# Sheet1.net
KiCad netlist of a schematic drawn in Altium Designer
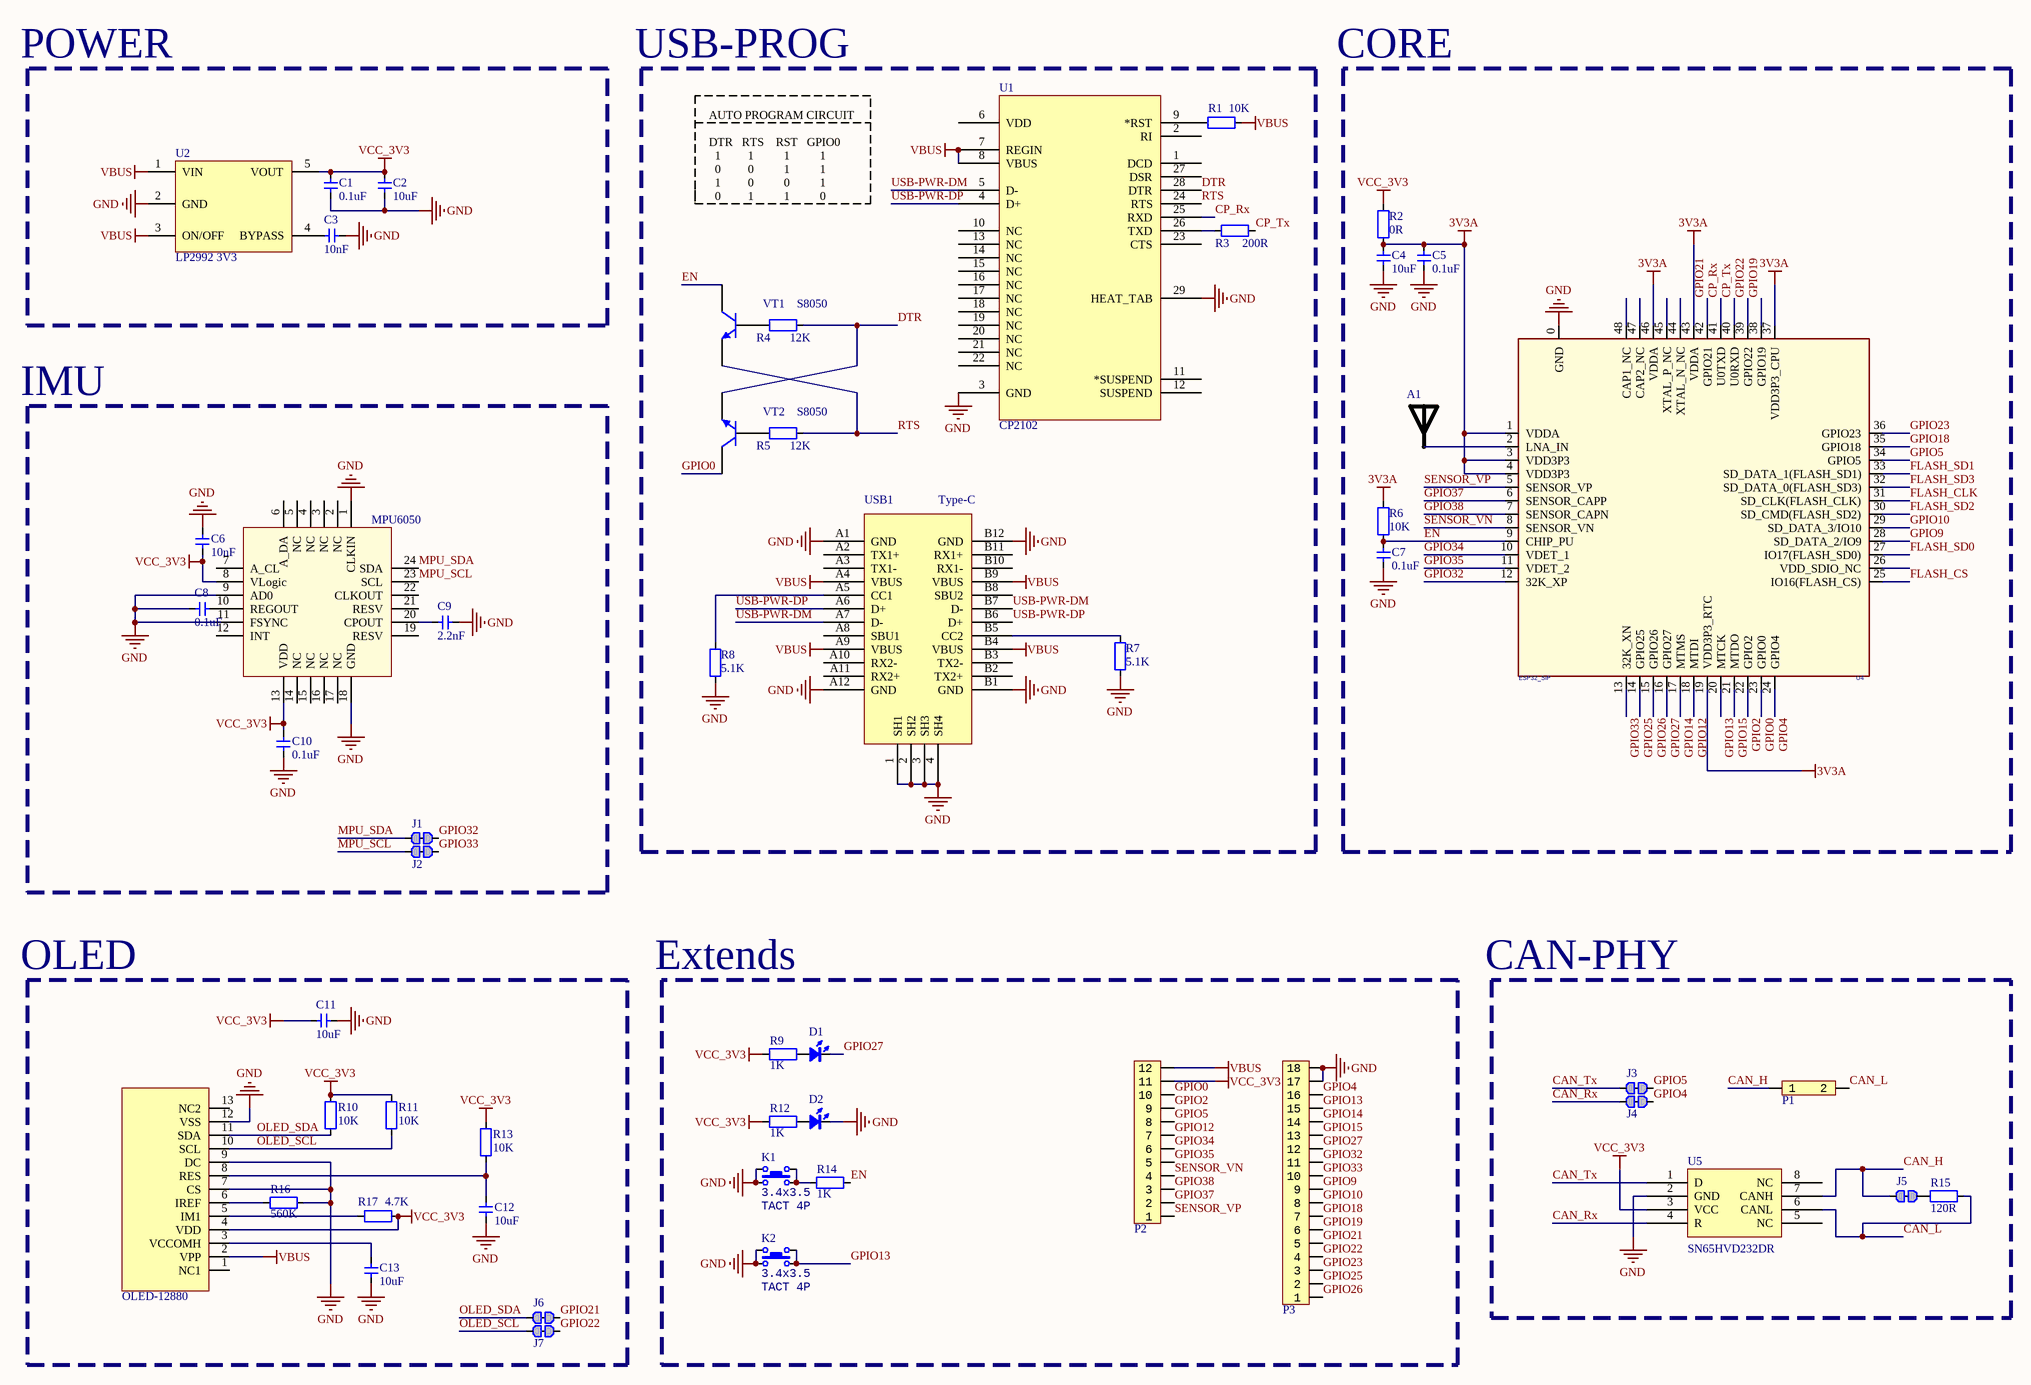
[diagram p0: Sheet1.SchDoc]

(export (version "E")
  (design (tool "Eeschema 10.0.6"))
  (components
    (comp (ref "1")
      (value "OLED-12880")
      (footprint "OLED-12880")
      (libsource (lib "mLib") (part "OLED-12880"))
    )
    (comp (ref "A1")
      (value "RAINSUN")
      (footprint "ANT-Rainsun-AN5120")
      (libsource (lib "MyPcbLib") (part "ANT-Rainsun-AP5120"))
    )
    (comp (ref "C1")
      (value "0.1uF")
      (footprint "C0603")
      (description "Capacitor")
      (libsource (lib "MyPcbLib") (part "电容-0402"))
    )
    (comp (ref "C2")
      (value "10uF")
      (footprint "C0603")
      (description "Capacitor")
      (libsource (lib "MyPcbLib") (part "电容-0402"))
    )
    (comp (ref "C3")
      (value "10nF")
      (footprint "C0603")
      (description "Capacitor")
      (libsource (lib "MyPcbLib") (part "电容-0402"))
    )
    (comp (ref "C4")
      (value "10uF")
      (footprint "C0603")
      (description "Capacitor")
      (libsource (lib "MyPcbLib") (part "电容-0402"))
    )
    (comp (ref "C5")
      (value "0.1uF")
      (footprint "C0603")
      (description "Capacitor")
      (libsource (lib "MyPcbLib") (part "电容-0402"))
    )
    (comp (ref "C6")
      (value "10nF")
      (footprint "C0603")
      (description "Capacitor")
      (libsource (lib "MyPcbLib") (part "电容-0402"))
    )
    (comp (ref "C7")
      (value "0.1uF")
      (footprint "C0603")
      (description "Capacitor")
      (libsource (lib "MyPcbLib") (part "电容-0402"))
    )
    (comp (ref "C8")
      (value "0.1uF")
      (footprint "C0603")
      (description "Capacitor")
      (libsource (lib "MyPcbLib") (part "电容-0402"))
    )
    (comp (ref "C9")
      (value "2.2nF")
      (footprint "C0603")
      (description "Capacitor")
      (libsource (lib "MyPcbLib") (part "电容-0402"))
    )
    (comp (ref "C10")
      (value "0.1uF")
      (footprint "C0603")
      (description "Capacitor")
      (libsource (lib "MyPcbLib") (part "电容-0402"))
    )
    (comp (ref "C11")
      (value "10uF")
      (footprint "C0603")
      (description "Capacitor")
      (libsource (lib "MyPcbLib") (part "电容-0402"))
    )
    (comp (ref "C12")
      (value "10uF")
      (footprint "C0603")
      (description "Capacitor")
      (libsource (lib "MyPcbLib") (part "电容-0402"))
    )
    (comp (ref "C13")
      (value "10uF")
      (footprint "C0603")
      (description "Capacitor")
      (libsource (lib "MyPcbLib") (part "电容-0402"))
    )
    (comp (ref "D1")
      (value "color?")
      (footprint "LED 0603")
      (description "LED")
      (libsource (lib "KitSprout") (part "LED_0402"))
    )
    (comp (ref "D2")
      (value "color?")
      (footprint "LED 0603")
      (description "LED")
      (libsource (lib "KitSprout") (part "LED_0402"))
    )
    (comp (ref "J1")
      (value "跳线")
      (footprint "R0603")
      (description "Resistor")
      (fields (field (name "PUBLISHER") "Altium Limited"))
      (libsource (lib "MyPcbLib") (part "跳线"))
    )
    (comp (ref "J2")
      (value "跳线")
      (footprint "R0603")
      (description "Resistor")
      (fields (field (name "PUBLISHER") "Altium Limited"))
      (libsource (lib "MyPcbLib") (part "跳线"))
    )
    (comp (ref "J3")
      (value "跳线")
      (footprint "R0603")
      (description "Resistor")
      (fields (field (name "PUBLISHER") "Altium Limited"))
      (libsource (lib "MyPcbLib") (part "跳线"))
    )
    (comp (ref "J4")
      (value "跳线")
      (footprint "R0603")
      (description "Resistor")
      (fields (field (name "PUBLISHER") "Altium Limited"))
      (libsource (lib "MyPcbLib") (part "跳线"))
    )
    (comp (ref "J5")
      (value "跳线")
      (footprint "R0603")
      (description "Resistor")
      (fields (field (name "PUBLISHER") "Altium Limited"))
      (libsource (lib "MyPcbLib") (part "跳线"))
    )
    (comp (ref "J6")
      (value "跳线")
      (footprint "R0603")
      (description "Resistor")
      (fields (field (name "PUBLISHER") "Altium Limited"))
      (libsource (lib "MyPcbLib") (part "跳线"))
    )
    (comp (ref "J7")
      (value "跳线")
      (footprint "R0603")
      (description "Resistor")
      (fields (field (name "PUBLISHER") "Altium Limited"))
      (libsource (lib "MyPcbLib") (part "跳线"))
    )
    (comp (ref "K1")
      (value "3.4x3.5")
      (footprint "ButtonTACT_3.5*3.55_90")
      (description "Button")
      (fields (field (name "TYPE") "TACT 4P") (field (name "Comment") "TACT 4P"))
      (libsource (lib "KitSprout") (part "ButtonTACT"))
    )
    (comp (ref "K2")
      (value "3.4x3.5")
      (footprint "ButtonTACT_3.5*3.55_90")
      (description "Button")
      (fields (field (name "TYPE") "TACT 4P") (field (name "Comment") "TACT 4P"))
      (libsource (lib "KitSprout") (part "ButtonTACT"))
    )
    (comp (ref "P1")
      (value "HDR2x1_2.54")
      (footprint "HDR1X2_2.54_180")
      (description "Header")
      (libsource (lib "KitSprout") (part "HDR2x1_2.54"))
    )
    (comp (ref "P2")
      (value "HDR1x12_2.54")
      (footprint "HDR1X12_2.54_180")
      (description "Header")
      (libsource (lib "KitSprout") (part "HDR1x12_2.54"))
    )
    (comp (ref "P3")
      (value "HDR1x18_2.54")
      (footprint "HDR1X18_2.54_180")
      (description "Header")
      (libsource (lib "KitSprout") (part "HDR1x18_2.54"))
    )
    (comp (ref "R1")
      (value "10K")
      (footprint "R0603")
      (description "Resistor")
      (libsource (lib "") (part "电阻-0402_2"))
    )
    (comp (ref "R2")
      (value "0R")
      (footprint "R0603")
      (description "Resistor")
      (libsource (lib "MyPcbLib") (part "电阻-0402"))
    )
    (comp (ref "R3")
      (value "200R")
      (footprint "R0603")
      (description "Resistor")
      (libsource (lib "") (part "电阻-0402_2"))
    )
    (comp (ref "R4")
      (value "12K")
      (footprint "R0603")
      (description "Resistor")
      (libsource (lib "") (part "电阻-0402_2"))
    )
    (comp (ref "R5")
      (value "12K")
      (footprint "R0603")
      (description "Resistor")
      (libsource (lib "") (part "电阻-0402_2"))
    )
    (comp (ref "R6")
      (value "10K")
      (footprint "R0603")
      (description "Resistor")
      (libsource (lib "MyPcbLib") (part "电阻-0402"))
    )
    (comp (ref "R7")
      (value "5.1K")
      (footprint "R0603")
      (description "Resistor")
      (libsource (lib "MyPcbLib") (part "电阻-0402"))
    )
    (comp (ref "R8")
      (value "5.1K")
      (footprint "R0603")
      (description "Resistor")
      (libsource (lib "MyPcbLib") (part "电阻-0402"))
    )
    (comp (ref "R9")
      (value "1K")
      (footprint "R0603")
      (description "Resistor")
      (libsource (lib "") (part "电阻-0402_1"))
    )
    (comp (ref "R10")
      (value "10K")
      (footprint "R0603")
      (description "Resistor")
      (libsource (lib "") (part "电阻-0402_3"))
    )
    (comp (ref "R11")
      (value "10K")
      (footprint "R0603")
      (description "Resistor")
      (libsource (lib "") (part "电阻-0402_3"))
    )
    (comp (ref "R12")
      (value "1K")
      (footprint "R0603")
      (description "Resistor")
      (libsource (lib "") (part "电阻-0402_1"))
    )
    (comp (ref "R13")
      (value "10K")
      (footprint "R0603")
      (description "Resistor")
      (libsource (lib "") (part "电阻-0402_3"))
    )
    (comp (ref "R14")
      (value "1K")
      (footprint "R0603")
      (description "Resistor")
      (libsource (lib "") (part "电阻-0402_1"))
    )
    (comp (ref "R15")
      (value "120R")
      (footprint "R0603")
      (description "Resistor")
      (libsource (lib "") (part "电阻-0402_1"))
    )
    (comp (ref "R16")
      (value "560K")
      (footprint "R0603")
      (description "Resistor")
      (libsource (lib "") (part "电阻-0402_1"))
    )
    (comp (ref "R17")
      (value "4.7K")
      (footprint "R0603")
      (description "Resistor")
      (libsource (lib "") (part "电阻-0402_1"))
    )
    (comp (ref "U1")
      (value "CP2102")
      (footprint "QFN-28")
      (description "USB转TTL")
      (libsource (lib "mLib") (part "CP2102"))
    )
    (comp (ref "U2")
      (value "LP2992 3V3")
      (footprint "SOT23-5")
      (description "LDO")
      (libsource (lib "MyPcbLib") (part "LP2992"))
    )
    (comp (ref "U3")
      (value "MPU6050")
      (footprint "QFN-24")
      (description "六轴传感器")
      (libsource (lib "mLib") (part "MPU6050"))
    )
    (comp (ref "U4")
      (value "ESP32_SIP")
      (footprint "QFN-48_7X7")
      (libsource (lib "MyPcbLib") (part "ESP32-PICO"))
    )
    (comp (ref "U5")
      (value "SN65HVD232D")
      (footprint "SO-8")
      (fields
        (field (name "MANUFACTURER") "Texas Instruments")
        (field (name "MANUFACTURER PART NUMBER") "SN65HVD232DR")
      )
      (libsource (lib "MyPcbLib") (part "SN65HVD232D"))
    )
    (comp (ref "USB1")
      (value "Type-C")
      (footprint "Type-C-TOP")
      (libsource (lib "MyPcbLib") (part "USB-Type-C-TOP"))
    )
    (comp (ref "VT1")
      (value "S8050")
      (footprint "SMT_TRIODE_NPN")
      (description "Surface mount NPN transistor, package SOT-23")
      (libsource (lib "MyPcbLib") (part "SMT_TRIODE_NPN"))
    )
    (comp (ref "VT2")
      (value "S8050")
      (footprint "SMT_TRIODE_NPN")
      (description "Surface mount NPN transistor, package SOT-23")
      (libsource (lib "MyPcbLib") (part "SMT_TRIODE_NPN"))
    )
  )
  (nets
    (net (code "1") (name "/CAN_H") (class "Default")
      (node (ref "J5") (pin "1") (pinfunction "1_1") (pintype "passive"))
      (node (ref "P1") (pin "1") (pinfunction "1_1") (pintype "passive"))
      (node (ref "U5") (pin "7") (pinfunction "CANH_7") (pintype "passive"))
    )
    (net (code "2") (name "/CAN_L") (class "Default")
      (node (ref "P1") (pin "2") (pinfunction "2_2") (pintype "passive"))
      (node (ref "R15") (pin "2") (pinfunction "2_2") (pintype "passive"))
      (node (ref "U5") (pin "6") (pinfunction "CANL_6") (pintype "passive"))
    )
    (net (code "3") (name "/CAN_Rx") (class "Default")
      (node (ref "J4") (pin "1") (pinfunction "1_1") (pintype "passive"))
      (node (ref "U5") (pin "4") (pinfunction "R_4") (pintype "passive"))
    )
    (net (code "4") (name "/CAN_Tx") (class "Default")
      (node (ref "J3") (pin "1") (pinfunction "1_1") (pintype "passive"))
      (node (ref "U5") (pin "1") (pinfunction "D_1") (pintype "passive"))
    )
    (net (code "5") (name "/CP_Rx") (class "Default")
      (node (ref "U1") (pin "25") (pinfunction "RXD_25") (pintype "passive"))
      (node (ref "U4") (pin "41") (pinfunction "U0TXD_41") (pintype "power_in"))
    )
    (net (code "6") (name "/CP_Tx") (class "Default")
      (node (ref "R3") (pin "1") (pinfunction "1_1") (pintype "passive"))
      (node (ref "U4") (pin "40") (pinfunction "U0RXD_40") (pintype "power_in"))
    )
    (net (code "7") (name "/DTR") (class "Default")
      (node (ref "R4") (pin "1") (pinfunction "1_1") (pintype "passive"))
      (node (ref "U1") (pin "28") (pinfunction "DTR_28") (pintype "passive"))
      (node (ref "VT2") (pin "2") (pinfunction "E_2") (pintype "passive"))
    )
    (net (code "8") (name "/EN") (class "Default")
      (node (ref "C7") (pin "1") (pinfunction "1_1") (pintype "passive"))
      (node (ref "R14") (pin "2") (pinfunction "2_2") (pintype "passive"))
      (node (ref "R6") (pin "2") (pinfunction "2_2") (pintype "passive"))
      (node (ref "U4") (pin "9") (pinfunction "CHIP_PU_9") (pintype "passive"))
      (node (ref "VT1") (pin "3") (pinfunction "C_3") (pintype "passive"))
    )
    (net (code "9") (name "/FLASH_CLK") (class "Default")
      (node (ref "U4") (pin "31") (pinfunction "SD_CLK(FLASH_CLK)_31") (pintype "passive"))
    )
    (net (code "10") (name "/FLASH_CS") (class "Default")
      (node (ref "U4") (pin "25") (pinfunction "IO16(FLASH_CS)_25") (pintype "passive"))
    )
    (net (code "11") (name "/FLASH_SD0") (class "Default")
      (node (ref "U4") (pin "27") (pinfunction "IO17(FLASH_SD0)_27") (pintype "passive"))
    )
    (net (code "12") (name "/FLASH_SD1") (class "Default")
      (node (ref "U4") (pin "33") (pinfunction "SD_DATA_1(FLASH_SD1)_33") (pintype "passive"))
    )
    (net (code "13") (name "/FLASH_SD2") (class "Default")
      (node (ref "U4") (pin "30") (pinfunction "SD_CMD(FLASH_SD2)_30") (pintype "passive"))
    )
    (net (code "14") (name "/FLASH_SD3") (class "Default")
      (node (ref "U4") (pin "32") (pinfunction "SD_DATA_0(FLASH_SD3)_32") (pintype "passive"))
    )
    (net (code "15") (name "/GPIO0") (class "Default")
      (node (ref "P2") (pin "10") (pinfunction "10_10") (pintype "passive"))
      (node (ref "U4") (pin "23") (pinfunction "GPIO0_23") (pintype "passive"))
      (node (ref "VT2") (pin "3") (pinfunction "C_3") (pintype "passive"))
    )
    (net (code "16") (name "/GPIO2") (class "Default")
      (node (ref "P2") (pin "9") (pinfunction "9_9") (pintype "passive"))
      (node (ref "U4") (pin "22") (pinfunction "GPIO2_22") (pintype "passive"))
    )
    (net (code "17") (name "/GPIO4") (class "Default")
      (node (ref "J4") (pin "2") (pinfunction "2_2") (pintype "passive"))
      (node (ref "P3") (pin "16") (pinfunction "16_16") (pintype "passive"))
      (node (ref "U4") (pin "24") (pinfunction "GPIO4_24") (pintype "passive"))
    )
    (net (code "18") (name "/GPIO5") (class "Default")
      (node (ref "J3") (pin "2") (pinfunction "2_2") (pintype "passive"))
      (node (ref "P2") (pin "8") (pinfunction "8_8") (pintype "passive"))
      (node (ref "U4") (pin "34") (pinfunction "GPIO5_34") (pintype "passive"))
    )
    (net (code "19") (name "/GPIO9") (class "Default")
      (node (ref "P3") (pin "9") (pinfunction "9_9") (pintype "passive"))
      (node (ref "U4") (pin "28") (pinfunction "SD_DATA_2/IO9_28") (pintype "passive"))
    )
    (net (code "20") (name "/GPIO10") (class "Default")
      (node (ref "P3") (pin "8") (pinfunction "8_8") (pintype "passive"))
      (node (ref "U4") (pin "29") (pinfunction "SD_DATA_3/IO10_29") (pintype "passive"))
    )
    (net (code "21") (name "/GPIO12") (class "Default")
      (node (ref "P2") (pin "7") (pinfunction "7_7") (pintype "passive"))
      (node (ref "U4") (pin "18") (pinfunction "MTDI_18") (pintype "passive"))
    )
    (net (code "22") (name "/GPIO13") (class "Default")
      (node (ref "K2") (pin "2") (pinfunction "2_2") (pintype "passive"))
      (node (ref "K2") (pin "4") (pinfunction "4_4") (pintype "passive"))
      (node (ref "P3") (pin "15") (pinfunction "15_15") (pintype "passive"))
      (node (ref "U4") (pin "20") (pinfunction "MTCK_20") (pintype "passive"))
    )
    (net (code "23") (name "/GPIO14") (class "Default")
      (node (ref "P3") (pin "14") (pinfunction "14_14") (pintype "passive"))
      (node (ref "U4") (pin "17") (pinfunction "MTMS_17") (pintype "passive"))
    )
    (net (code "24") (name "/GPIO15") (class "Default")
      (node (ref "P3") (pin "13") (pinfunction "13_13") (pintype "passive"))
      (node (ref "U4") (pin "21") (pinfunction "MTDO_21") (pintype "passive"))
    )
    (net (code "25") (name "/GPIO18") (class "Default")
      (node (ref "P3") (pin "7") (pinfunction "7_7") (pintype "passive"))
      (node (ref "U4") (pin "35") (pinfunction "GPIO18_35") (pintype "passive"))
    )
    (net (code "26") (name "/GPIO19") (class "Default")
      (node (ref "P3") (pin "6") (pinfunction "6_6") (pintype "passive"))
      (node (ref "U4") (pin "38") (pinfunction "GPIO19_38") (pintype "passive"))
    )
    (net (code "27") (name "/GPIO21") (class "Default")
      (node (ref "J6") (pin "2") (pinfunction "2_2") (pintype "passive"))
      (node (ref "P3") (pin "5") (pinfunction "5_5") (pintype "passive"))
      (node (ref "U4") (pin "42") (pinfunction "GPIO21_42") (pintype "passive"))
    )
    (net (code "28") (name "/GPIO22") (class "Default")
      (node (ref "J7") (pin "2") (pinfunction "2_2") (pintype "passive"))
      (node (ref "P3") (pin "4") (pinfunction "4_4") (pintype "passive"))
      (node (ref "U4") (pin "39") (pinfunction "GPIO22_39") (pintype "passive"))
    )
    (net (code "29") (name "/GPIO23") (class "Default")
      (node (ref "P3") (pin "3") (pinfunction "3_3") (pintype "passive"))
      (node (ref "U4") (pin "36") (pinfunction "GPIO23_36") (pintype "passive"))
    )
    (net (code "30") (name "/GPIO25") (class "Default")
      (node (ref "P3") (pin "2") (pinfunction "2_2") (pintype "passive"))
      (node (ref "U4") (pin "14") (pinfunction "GPIO25_14") (pintype "passive"))
    )
    (net (code "31") (name "/GPIO26") (class "Default")
      (node (ref "P3") (pin "1") (pinfunction "1_1") (pintype "passive"))
      (node (ref "U4") (pin "15") (pinfunction "GPIO26_15") (pintype "passive"))
    )
    (net (code "32") (name "/GPIO27") (class "Default")
      (node (ref "D1") (pin "2") (pinfunction "K_2") (pintype "passive"))
      (node (ref "P3") (pin "12") (pinfunction "12_12") (pintype "passive"))
      (node (ref "U4") (pin "16") (pinfunction "GPIO27_16") (pintype "passive"))
    )
    (net (code "33") (name "/GPIO32") (class "Default")
      (node (ref "J1") (pin "2") (pinfunction "2_2") (pintype "passive"))
      (node (ref "P3") (pin "11") (pinfunction "11_11") (pintype "passive"))
      (node (ref "U4") (pin "12") (pinfunction "32K_XP_12") (pintype "passive"))
    )
    (net (code "34") (name "/GPIO33") (class "Default")
      (node (ref "J2") (pin "2") (pinfunction "2_2") (pintype "passive"))
      (node (ref "P3") (pin "10") (pinfunction "10_10") (pintype "passive"))
      (node (ref "U4") (pin "13") (pinfunction "32K_XN_13") (pintype "passive"))
    )
    (net (code "35") (name "/GPIO34") (class "Default")
      (node (ref "P2") (pin "6") (pinfunction "6_6") (pintype "passive"))
      (node (ref "U4") (pin "10") (pinfunction "VDET_1_10") (pintype "passive"))
    )
    (net (code "36") (name "/GPIO35") (class "Default")
      (node (ref "P2") (pin "5") (pinfunction "5_5") (pintype "passive"))
      (node (ref "U4") (pin "11") (pinfunction "VDET_2_11") (pintype "passive"))
    )
    (net (code "37") (name "/GPIO37") (class "Default")
      (node (ref "P2") (pin "2") (pinfunction "2_2") (pintype "passive"))
      (node (ref "U4") (pin "6") (pinfunction "SENSOR_CAPP_6") (pintype "passive"))
    )
    (net (code "38") (name "/GPIO38") (class "Default")
      (node (ref "P2") (pin "3") (pinfunction "3_3") (pintype "passive"))
      (node (ref "U4") (pin "7") (pinfunction "SENSOR_CAPN_7") (pintype "passive"))
    )
    (net (code "39") (name "/MPU_SCL") (class "Default")
      (node (ref "J2") (pin "1") (pinfunction "1_1") (pintype "passive"))
      (node (ref "U3") (pin "23") (pinfunction "SCL_23") (pintype "passive"))
    )
    (net (code "40") (name "/MPU_SDA") (class "Default")
      (node (ref "J1") (pin "1") (pinfunction "1_1") (pintype "passive"))
      (node (ref "U3") (pin "24") (pinfunction "SDA_24") (pintype "passive"))
    )
    (net (code "41") (name "/OLED_SCL") (class "Default")
      (node (ref "1") (pin "10") (pinfunction "SCL_10") (pintype "passive"))
      (node (ref "J7") (pin "1") (pinfunction "1_1") (pintype "passive"))
      (node (ref "R11") (pin "1") (pinfunction "1_1") (pintype "passive"))
    )
    (net (code "42") (name "/OLED_SDA") (class "Default")
      (node (ref "1") (pin "11") (pinfunction "SDA_11") (pintype "passive"))
      (node (ref "J6") (pin "1") (pinfunction "1_1") (pintype "passive"))
      (node (ref "R10") (pin "1") (pinfunction "1_1") (pintype "passive"))
    )
    (net (code "43") (name "/RTS") (class "Default")
      (node (ref "R5") (pin "1") (pinfunction "1_1") (pintype "passive"))
      (node (ref "U1") (pin "24") (pinfunction "RTS_24") (pintype "passive"))
      (node (ref "VT1") (pin "2") (pinfunction "E_2") (pintype "passive"))
    )
    (net (code "44") (name "/SENSOR_VN") (class "Default")
      (node (ref "P2") (pin "4") (pinfunction "4_4") (pintype "passive"))
      (node (ref "U4") (pin "8") (pinfunction "SENSOR_VN_8") (pintype "passive"))
    )
    (net (code "45") (name "/SENSOR_VP") (class "Default")
      (node (ref "P2") (pin "1") (pinfunction "1_1") (pintype "passive"))
      (node (ref "U4") (pin "5") (pinfunction "SENSOR_VP_5") (pintype "passive"))
    )
    (net (code "46") (name "/USB-PWR-DM") (class "Default")
      (node (ref "U1") (pin "5") (pinfunction "D-_5") (pintype "passive"))
      (node (ref "USB1") (pin "A7") (pinfunction "D-_A7") (pintype "passive"))
      (node (ref "USB1") (pin "B7") (pinfunction "D-_B7") (pintype "passive"))
    )
    (net (code "47") (name "/USB-PWR-DP") (class "Default")
      (node (ref "U1") (pin "4") (pinfunction "D+_4") (pintype "passive"))
      (node (ref "USB1") (pin "A6") (pinfunction "D+_A6") (pintype "passive"))
      (node (ref "USB1") (pin "B6") (pinfunction "D+_B6") (pintype "passive"))
    )
    (net (code "48") (name "3V3A") (class "Default")
      (node (ref "C4") (pin "2") (pinfunction "2_2") (pintype "passive"))
      (node (ref "C5") (pin "2") (pinfunction "2_2") (pintype "passive"))
      (node (ref "R2") (pin "2") (pinfunction "2_2") (pintype "passive"))
      (node (ref "R6") (pin "1") (pinfunction "1_1") (pintype "passive"))
      (node (ref "U4") (pin "1") (pinfunction "VDDA_1") (pintype "power_in"))
      (node (ref "U4") (pin "19") (pinfunction "VDD3P3_RTC_19") (pintype "power_in"))
      (node (ref "U4") (pin "3") (pinfunction "VDD3P3_3") (pintype "power_in"))
      (node (ref "U4") (pin "37") (pinfunction "VDD3P3_CPU_37") (pintype "power_in"))
      (node (ref "U4") (pin "4") (pinfunction "VDD3P3_4") (pintype "power_in"))
      (node (ref "U4") (pin "43") (pinfunction "VDDA_43") (pintype "power_in"))
      (node (ref "U4") (pin "46") (pinfunction "VDDA_46") (pintype "power_in"))
    )
    (net (code "49") (name "GND") (class "Default")
      (node (ref "1") (pin "12") (pinfunction "VSS_12") (pintype "passive"))
      (node (ref "1") (pin "7") (pinfunction "CS_7") (pintype "passive"))
      (node (ref "1") (pin "9") (pinfunction "DC_9") (pintype "passive"))
      (node (ref "C1") (pin "1") (pinfunction "1_1") (pintype "passive"))
      (node (ref "C10") (pin "1") (pinfunction "1_1") (pintype "passive"))
      (node (ref "C11") (pin "1") (pinfunction "1_1") (pintype "passive"))
      (node (ref "C12") (pin "1") (pinfunction "1_1") (pintype "passive"))
      (node (ref "C13") (pin "1") (pinfunction "1_1") (pintype "passive"))
      (node (ref "C2") (pin "1") (pinfunction "1_1") (pintype "passive"))
      (node (ref "C3") (pin "1") (pinfunction "1_1") (pintype "passive"))
      (node (ref "C4") (pin "1") (pinfunction "1_1") (pintype "passive"))
      (node (ref "C5") (pin "1") (pinfunction "1_1") (pintype "passive"))
      (node (ref "C6") (pin "2") (pinfunction "2_2") (pintype "passive"))
      (node (ref "C7") (pin "2") (pinfunction "2_2") (pintype "passive"))
      (node (ref "C8") (pin "2") (pinfunction "2_2") (pintype "passive"))
      (node (ref "C9") (pin "1") (pinfunction "1_1") (pintype "passive"))
      (node (ref "D2") (pin "2") (pinfunction "K_2") (pintype "passive"))
      (node (ref "K1") (pin "1") (pinfunction "1_1") (pintype "passive"))
      (node (ref "K1") (pin "3") (pinfunction "3_3") (pintype "passive"))
      (node (ref "K2") (pin "1") (pinfunction "1_1") (pintype "passive"))
      (node (ref "K2") (pin "3") (pinfunction "3_3") (pintype "passive"))
      (node (ref "P3") (pin "17") (pinfunction "17_17") (pintype "passive"))
      (node (ref "P3") (pin "18") (pinfunction "18_18") (pintype "passive"))
      (node (ref "R16") (pin "2") (pinfunction "2_2") (pintype "passive"))
      (node (ref "R7") (pin "2") (pinfunction "2_2") (pintype "passive"))
      (node (ref "R8") (pin "2") (pinfunction "2_2") (pintype "passive"))
      (node (ref "U1") (pin "29") (pinfunction "HEAT_TAB_29") (pintype "passive"))
      (node (ref "U1") (pin "3") (pinfunction "GND_3") (pintype "passive"))
      (node (ref "U2") (pin "2") (pinfunction "GND_2") (pintype "passive"))
      (node (ref "U3") (pin "1") (pinfunction "CLKIN_1") (pintype "passive"))
      (node (ref "U3") (pin "11") (pinfunction "FSYNC_11") (pintype "passive"))
      (node (ref "U3") (pin "18") (pinfunction "GND_18") (pintype "passive"))
      (node (ref "U3") (pin "9") (pinfunction "AD0_9") (pintype "passive"))
      (node (ref "U4") (pin "0") (pinfunction "GND_0") (pintype "power_in"))
      (node (ref "U5") (pin "2") (pinfunction "GND_2") (pintype "passive"))
      (node (ref "USB1") (pin "1") (pinfunction "SH1_1") (pintype "passive"))
      (node (ref "USB1") (pin "2") (pinfunction "SH2_2") (pintype "passive"))
      (node (ref "USB1") (pin "3") (pinfunction "SH3_3") (pintype "passive"))
      (node (ref "USB1") (pin "4") (pinfunction "SH4_4") (pintype "passive"))
      (node (ref "USB1") (pin "A1") (pinfunction "GND_A1") (pintype "passive"))
      (node (ref "USB1") (pin "A12") (pinfunction "GND_A12") (pintype "passive"))
      (node (ref "USB1") (pin "B1") (pinfunction "GND_B1") (pintype "passive"))
      (node (ref "USB1") (pin "B12") (pinfunction "GND_B12") (pintype "passive"))
    )
    (net (code "50") (name "Net-(1-IM1)") (class "Default")
      (node (ref "1") (pin "5") (pinfunction "IM1_5") (pintype "passive"))
      (node (ref "R17") (pin "1") (pinfunction "1_1") (pintype "passive"))
    )
    (net (code "51") (name "Net-(1-IREF)") (class "Default")
      (node (ref "1") (pin "6") (pinfunction "IREF_6") (pintype "passive"))
      (node (ref "R16") (pin "1") (pinfunction "1_1") (pintype "passive"))
    )
    (net (code "52") (name "Net-(1-RES)") (class "Default")
      (node (ref "1") (pin "8") (pinfunction "RES_8") (pintype "passive"))
      (node (ref "C12") (pin "2") (pinfunction "2_2") (pintype "passive"))
      (node (ref "R13") (pin "1") (pinfunction "1_1") (pintype "passive"))
    )
    (net (code "53") (name "Net-(1-VCCOMH)") (class "Default")
      (node (ref "1") (pin "3") (pinfunction "VCCOMH_3") (pintype "passive"))
      (node (ref "C13") (pin "2") (pinfunction "2_2") (pintype "passive"))
    )
    (net (code "54") (name "Net-(D1-A)") (class "Default")
      (node (ref "D1") (pin "1") (pinfunction "A_1") (pintype "passive"))
      (node (ref "R9") (pin "2") (pinfunction "2_2") (pintype "passive"))
    )
    (net (code "55") (name "Net-(D2-A)") (class "Default")
      (node (ref "D2") (pin "1") (pinfunction "A_1") (pintype "passive"))
      (node (ref "R12") (pin "2") (pinfunction "2_2") (pintype "passive"))
    )
    (net (code "56") (name "Net-(J5-Pad2)") (class "Default")
      (node (ref "J5") (pin "2") (pinfunction "2_2") (pintype "passive"))
      (node (ref "R15") (pin "1") (pinfunction "1_1") (pintype "passive"))
    )
    (net (code "57") (name "Net-(K1-Pad2)") (class "Default")
      (node (ref "K1") (pin "2") (pinfunction "2_2") (pintype "passive"))
      (node (ref "K1") (pin "4") (pinfunction "4_4") (pintype "passive"))
      (node (ref "R14") (pin "1") (pinfunction "1_1") (pintype "passive"))
    )
    (net (code "58") (name "Net-(U1-*RST)") (class "Default")
      (node (ref "R1") (pin "2") (pinfunction "2_2") (pintype "passive"))
      (node (ref "U1") (pin "9") (pinfunction "*RST_9") (pintype "passive"))
    )
    (net (code "59") (name "Net-(U1-TXD)") (class "Default")
      (node (ref "R3") (pin "2") (pinfunction "2_2") (pintype "passive"))
      (node (ref "U1") (pin "26") (pinfunction "TXD_26") (pintype "passive"))
    )
    (net (code "60") (name "Net-(U2-BYPASS)") (class "Default")
      (node (ref "C3") (pin "2") (pinfunction "2_2") (pintype "passive"))
      (node (ref "U2") (pin "4") (pinfunction "BYPASS_4") (pintype "passive"))
    )
    (net (code "61") (name "Net-(U3-CPOUT)") (class "Default")
      (node (ref "C9") (pin "2") (pinfunction "2_2") (pintype "passive"))
      (node (ref "U3") (pin "20") (pinfunction "CPOUT_20") (pintype "passive"))
    )
    (net (code "62") (name "Net-(U3-REGOUT)") (class "Default")
      (node (ref "C8") (pin "1") (pinfunction "1_1") (pintype "passive"))
      (node (ref "U3") (pin "10") (pinfunction "REGOUT_10") (pintype "passive"))
    )
    (net (code "63") (name "Net-(U4-LNA_IN)") (class "Default")
      (node (ref "A1") (pin "1") (pinfunction "1_1") (pintype "passive"))
      (node (ref "U4") (pin "2") (pinfunction "LNA_IN_2") (pintype "passive"))
    )
    (net (code "64") (name "Net-(USB1-CC1)") (class "Default")
      (node (ref "R8") (pin "1") (pinfunction "1_1") (pintype "passive"))
      (node (ref "USB1") (pin "A5") (pinfunction "CC1_A5") (pintype "passive"))
    )
    (net (code "65") (name "Net-(USB1-CC2)") (class "Default")
      (node (ref "R7") (pin "1") (pinfunction "1_1") (pintype "passive"))
      (node (ref "USB1") (pin "B5") (pinfunction "CC2_B5") (pintype "passive"))
    )
    (net (code "66") (name "Net-(VT1-B)") (class "Default")
      (node (ref "R4") (pin "2") (pinfunction "2_2") (pintype "passive"))
      (node (ref "VT1") (pin "1") (pinfunction "B_1") (pintype "passive"))
    )
    (net (code "67") (name "Net-(VT2-B)") (class "Default")
      (node (ref "R5") (pin "2") (pinfunction "2_2") (pintype "passive"))
      (node (ref "VT2") (pin "1") (pinfunction "B_1") (pintype "passive"))
    )
    (net (code "68") (name "VBUS") (class "Default")
      (node (ref "1") (pin "2") (pinfunction "VPP_2") (pintype "passive"))
      (node (ref "P2") (pin "12") (pinfunction "12_12") (pintype "passive"))
      (node (ref "R1") (pin "1") (pinfunction "1_1") (pintype "passive"))
      (node (ref "U1") (pin "7") (pinfunction "REGIN_7") (pintype "passive"))
      (node (ref "U1") (pin "8") (pinfunction "VBUS_8") (pintype "passive"))
      (node (ref "U2") (pin "1") (pinfunction "VIN_1") (pintype "passive"))
      (node (ref "U2") (pin "3") (pinfunction "ON/OFF_3") (pintype "passive"))
      (node (ref "USB1") (pin "A4") (pinfunction "VBUS_A4") (pintype "passive"))
      (node (ref "USB1") (pin "A9") (pinfunction "VBUS_A9") (pintype "passive"))
      (node (ref "USB1") (pin "B4") (pinfunction "VBUS_B4") (pintype "passive"))
      (node (ref "USB1") (pin "B9") (pinfunction "VBUS_B9") (pintype "passive"))
    )
    (net (code "69") (name "VCC_3V3") (class "Default")
      (node (ref "1") (pin "4") (pinfunction "VDD_4") (pintype "passive"))
      (node (ref "C1") (pin "2") (pinfunction "2_2") (pintype "passive"))
      (node (ref "C10") (pin "2") (pinfunction "2_2") (pintype "passive"))
      (node (ref "C11") (pin "2") (pinfunction "2_2") (pintype "passive"))
      (node (ref "C2") (pin "2") (pinfunction "2_2") (pintype "passive"))
      (node (ref "C6") (pin "1") (pinfunction "1_1") (pintype "passive"))
      (node (ref "P2") (pin "11") (pinfunction "11_11") (pintype "passive"))
      (node (ref "R10") (pin "2") (pinfunction "2_2") (pintype "passive"))
      (node (ref "R11") (pin "2") (pinfunction "2_2") (pintype "passive"))
      (node (ref "R12") (pin "1") (pinfunction "1_1") (pintype "passive"))
      (node (ref "R13") (pin "2") (pinfunction "2_2") (pintype "passive"))
      (node (ref "R17") (pin "2") (pinfunction "2_2") (pintype "passive"))
      (node (ref "R2") (pin "1") (pinfunction "1_1") (pintype "passive"))
      (node (ref "R9") (pin "1") (pinfunction "1_1") (pintype "passive"))
      (node (ref "U2") (pin "5") (pinfunction "VOUT_5") (pintype "passive"))
      (node (ref "U3") (pin "13") (pinfunction "VDD_13") (pintype "passive"))
      (node (ref "U3") (pin "8") (pinfunction "VLogic_8") (pintype "passive"))
      (node (ref "U5") (pin "3") (pinfunction "VCC_3") (pintype "passive"))
    )
    (net (code "70") (name "unconnected-(1-NC1-Pad1)") (class "Default")
      (node (ref "1") (pin "1") (pinfunction "NC1_1") (pintype "passive"))
    )
    (net (code "71") (name "unconnected-(1-NC2-Pad13)") (class "Default")
      (node (ref "1") (pin "13") (pinfunction "NC2_13") (pintype "passive"))
    )
    (net (code "72") (name "unconnected-(U1-*SUSPEND-Pad11)") (class "Default")
      (node (ref "U1") (pin "11") (pinfunction "*SUSPEND_11") (pintype "passive"))
    )
    (net (code "73") (name "unconnected-(U1-CTS-Pad23)") (class "Default")
      (node (ref "U1") (pin "23") (pinfunction "CTS_23") (pintype "passive"))
    )
    (net (code "74") (name "unconnected-(U1-DCD-Pad1)") (class "Default")
      (node (ref "U1") (pin "1") (pinfunction "DCD_1") (pintype "passive"))
    )
    (net (code "75") (name "unconnected-(U1-DSR-Pad27)") (class "Default")
      (node (ref "U1") (pin "27") (pinfunction "DSR_27") (pintype "passive"))
    )
    (net (code "76") (name "unconnected-(U1-NC-Pad10)") (class "Default")
      (node (ref "U1") (pin "10") (pinfunction "NC_10") (pintype "passive"))
    )
    (net (code "77") (name "unconnected-(U1-NC-Pad13)") (class "Default")
      (node (ref "U1") (pin "13") (pinfunction "NC_13") (pintype "passive"))
    )
    (net (code "78") (name "unconnected-(U1-NC-Pad14)") (class "Default")
      (node (ref "U1") (pin "14") (pinfunction "NC_14") (pintype "passive"))
    )
    (net (code "79") (name "unconnected-(U1-NC-Pad15)") (class "Default")
      (node (ref "U1") (pin "15") (pinfunction "NC_15") (pintype "passive"))
    )
    (net (code "80") (name "unconnected-(U1-NC-Pad16)") (class "Default")
      (node (ref "U1") (pin "16") (pinfunction "NC_16") (pintype "passive"))
    )
    (net (code "81") (name "unconnected-(U1-NC-Pad17)") (class "Default")
      (node (ref "U1") (pin "17") (pinfunction "NC_17") (pintype "passive"))
    )
    (net (code "82") (name "unconnected-(U1-NC-Pad18)") (class "Default")
      (node (ref "U1") (pin "18") (pinfunction "NC_18") (pintype "passive"))
    )
    (net (code "83") (name "unconnected-(U1-NC-Pad19)") (class "Default")
      (node (ref "U1") (pin "19") (pinfunction "NC_19") (pintype "passive"))
    )
    (net (code "84") (name "unconnected-(U1-NC-Pad20)") (class "Default")
      (node (ref "U1") (pin "20") (pinfunction "NC_20") (pintype "passive"))
    )
    (net (code "85") (name "unconnected-(U1-NC-Pad21)") (class "Default")
      (node (ref "U1") (pin "21") (pinfunction "NC_21") (pintype "passive"))
    )
    (net (code "86") (name "unconnected-(U1-NC-Pad22)") (class "Default")
      (node (ref "U1") (pin "22") (pinfunction "NC_22") (pintype "passive"))
    )
    (net (code "87") (name "unconnected-(U1-RI-Pad2)") (class "Default")
      (node (ref "U1") (pin "2") (pinfunction "RI_2") (pintype "passive"))
    )
    (net (code "88") (name "unconnected-(U1-SUSPEND-Pad12)") (class "Default")
      (node (ref "U1") (pin "12") (pinfunction "SUSPEND_12") (pintype "passive"))
    )
    (net (code "89") (name "unconnected-(U1-VDD-Pad6)") (class "Default")
      (node (ref "U1") (pin "6") (pinfunction "VDD_6") (pintype "passive"))
    )
    (net (code "90") (name "unconnected-(U3-A_CL-Pad7)") (class "Default")
      (node (ref "U3") (pin "7") (pinfunction "A_CL_7") (pintype "passive"))
    )
    (net (code "91") (name "unconnected-(U3-A_DA-Pad6)") (class "Default")
      (node (ref "U3") (pin "6") (pinfunction "A_DA_6") (pintype "passive"))
    )
    (net (code "92") (name "unconnected-(U3-CLKOUT-Pad22)") (class "Default")
      (node (ref "U3") (pin "22") (pinfunction "CLKOUT_22") (pintype "passive"))
    )
    (net (code "93") (name "unconnected-(U3-INT-Pad12)") (class "Default")
      (node (ref "U3") (pin "12") (pinfunction "INT_12") (pintype "passive"))
    )
    (net (code "94") (name "unconnected-(U3-NC-Pad2)") (class "Default")
      (node (ref "U3") (pin "2") (pinfunction "NC_2") (pintype "passive"))
    )
    (net (code "95") (name "unconnected-(U3-NC-Pad3)") (class "Default")
      (node (ref "U3") (pin "3") (pinfunction "NC_3") (pintype "passive"))
    )
    (net (code "96") (name "unconnected-(U3-NC-Pad4)") (class "Default")
      (node (ref "U3") (pin "4") (pinfunction "NC_4") (pintype "passive"))
    )
    (net (code "97") (name "unconnected-(U3-NC-Pad5)") (class "Default")
      (node (ref "U3") (pin "5") (pinfunction "NC_5") (pintype "passive"))
    )
    (net (code "98") (name "unconnected-(U3-NC-Pad14)") (class "Default")
      (node (ref "U3") (pin "14") (pinfunction "NC_14") (pintype "passive"))
    )
    (net (code "99") (name "unconnected-(U3-NC-Pad15)") (class "Default")
      (node (ref "U3") (pin "15") (pinfunction "NC_15") (pintype "passive"))
    )
    (net (code "100") (name "unconnected-(U3-NC-Pad16)") (class "Default")
      (node (ref "U3") (pin "16") (pinfunction "NC_16") (pintype "passive"))
    )
    (net (code "101") (name "unconnected-(U3-NC-Pad17)") (class "Default")
      (node (ref "U3") (pin "17") (pinfunction "NC_17") (pintype "passive"))
    )
    (net (code "102") (name "unconnected-(U3-RESV-Pad19)") (class "Default")
      (node (ref "U3") (pin "19") (pinfunction "RESV_19") (pintype "passive"))
    )
    (net (code "103") (name "unconnected-(U3-RESV-Pad21)") (class "Default")
      (node (ref "U3") (pin "21") (pinfunction "RESV_21") (pintype "passive"))
    )
    (net (code "104") (name "unconnected-(U4-CAP1_NC-Pad48)") (class "Default")
      (node (ref "U4") (pin "48") (pinfunction "CAP1_NC_48") (pintype "passive"))
    )
    (net (code "105") (name "unconnected-(U4-CAP2_NC-Pad47)") (class "Default")
      (node (ref "U4") (pin "47") (pinfunction "CAP2_NC_47") (pintype "passive"))
    )
    (net (code "106") (name "unconnected-(U4-VDD_SDIO_NC-Pad26)") (class "Default")
      (node (ref "U4") (pin "26") (pinfunction "VDD_SDIO_NC_26") (pintype "passive"))
    )
    (net (code "107") (name "unconnected-(U4-XTAL_N_NC-Pad44)") (class "Default")
      (node (ref "U4") (pin "44") (pinfunction "XTAL_N_NC_44") (pintype "passive"))
    )
    (net (code "108") (name "unconnected-(U4-XTAL_P_NC-Pad45)") (class "Default")
      (node (ref "U4") (pin "45") (pinfunction "XTAL_P_NC_45") (pintype "passive"))
    )
    (net (code "109") (name "unconnected-(U5-NC-Pad5)") (class "Default")
      (node (ref "U5") (pin "5") (pinfunction "NC_5") (pintype "passive"))
    )
    (net (code "110") (name "unconnected-(U5-NC-Pad8)") (class "Default")
      (node (ref "U5") (pin "8") (pinfunction "NC_8") (pintype "passive"))
    )
    (net (code "111") (name "unconnected-(USB1-RX1+-PadB11)") (class "Default")
      (node (ref "USB1") (pin "B11") (pinfunction "RX1+_B11") (pintype "passive"))
    )
    (net (code "112") (name "unconnected-(USB1-RX1--PadB10)") (class "Default")
      (node (ref "USB1") (pin "B10") (pinfunction "RX1-_B10") (pintype "passive"))
    )
    (net (code "113") (name "unconnected-(USB1-RX2+-PadA11)") (class "Default")
      (node (ref "USB1") (pin "A11") (pinfunction "RX2+_A11") (pintype "passive"))
    )
    (net (code "114") (name "unconnected-(USB1-RX2--PadA10)") (class "Default")
      (node (ref "USB1") (pin "A10") (pinfunction "RX2-_A10") (pintype "passive"))
    )
    (net (code "115") (name "unconnected-(USB1-SBU1-PadA8)") (class "Default")
      (node (ref "USB1") (pin "A8") (pinfunction "SBU1_A8") (pintype "passive"))
    )
    (net (code "116") (name "unconnected-(USB1-SBU2-PadB8)") (class "Default")
      (node (ref "USB1") (pin "B8") (pinfunction "SBU2_B8") (pintype "passive"))
    )
    (net (code "117") (name "unconnected-(USB1-TX1+-PadA2)") (class "Default")
      (node (ref "USB1") (pin "A2") (pinfunction "TX1+_A2") (pintype "passive"))
    )
    (net (code "118") (name "unconnected-(USB1-TX1--PadA3)") (class "Default")
      (node (ref "USB1") (pin "A3") (pinfunction "TX1-_A3") (pintype "passive"))
    )
    (net (code "119") (name "unconnected-(USB1-TX2+-PadB2)") (class "Default")
      (node (ref "USB1") (pin "B2") (pinfunction "TX2+_B2") (pintype "passive"))
    )
    (net (code "120") (name "unconnected-(USB1-TX2--PadB3)") (class "Default")
      (node (ref "USB1") (pin "B3") (pinfunction "TX2-_B3") (pintype "passive"))
    )
  )
)
